# MainBoard_HMI.net
KiCad netlist of a schematic drawn in Altium Designer
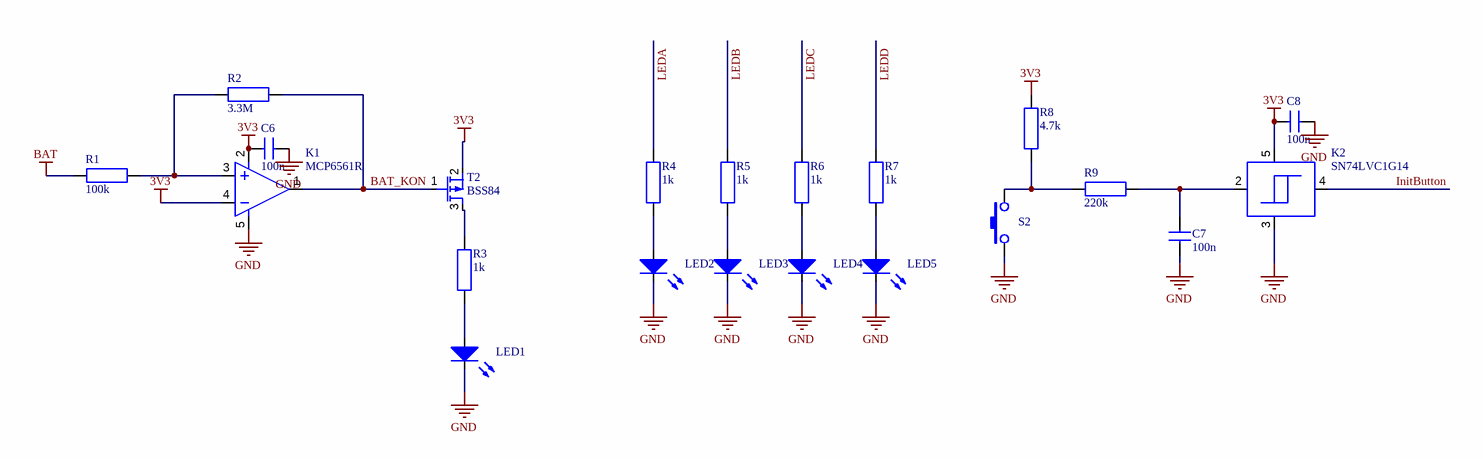
[diagram p0: MainBoard_HMI.SchDoc]

(export (version "E")
  (design (tool "Eeschema 10.0.6"))
  (components
    (comp (ref "C6")
      (value "100n")
      (footprint "0805_C")
      (description "Normaler Kondensator")
      (libsource (lib "MainBoard") (part "C?"))
    )
    (comp (ref "C7")
      (value "100n")
      (footprint "0805_C")
      (description "Normaler Kondensator")
      (libsource (lib "MainBoard") (part "C?"))
    )
    (comp (ref "C8")
      (value "100n")
      (footprint "0805_C")
      (description "Normaler Kondensator")
      (libsource (lib "MainBoard") (part "C?"))
    )
    (comp (ref "K1") (value "MCP6561R") (footprint "SOT23-5") (libsource (lib "MainBoard") (part "OPAMP")))
    (comp (ref "K2")
      (value "SN74LVC1G14")
      (footprint "SOT23-5")
      (libsource (lib "MainBoard") (part "schmitt"))
    )
    (comp (ref "LED1")
      (value "~")
      (footprint "LED_THT_3mm_RM_2.54mm")
      (libsource (lib "Sch_Lib") (part "LED"))
    )
    (comp (ref "LED2")
      (value "~")
      (footprint "LED_THT_3mm_RM_2.54mm")
      (libsource (lib "Sch_Lib") (part "LED"))
    )
    (comp (ref "LED3")
      (value "~")
      (footprint "LED_THT_3mm_RM_2.54mm")
      (libsource (lib "Sch_Lib") (part "LED"))
    )
    (comp (ref "LED4")
      (value "~")
      (footprint "LED_THT_3mm_RM_2.54mm")
      (libsource (lib "Sch_Lib") (part "LED"))
    )
    (comp (ref "LED5")
      (value "~")
      (footprint "LED_THT_3mm_RM_2.54mm")
      (libsource (lib "Sch_Lib") (part "LED"))
    )
    (comp (ref "R1")
      (value "100k")
      (footprint "0805_R")
      (description "Normaler Widerstand")
      (libsource (lib "MainBoard") (part "R?"))
    )
    (comp (ref "R2")
      (value "3.3M")
      (footprint "0805_R")
      (description "Normaler Widerstand")
      (libsource (lib "MainBoard") (part "R?"))
    )
    (comp (ref "R3")
      (value "1k")
      (footprint "0805_R")
      (description "Normaler Widerstand")
      (libsource (lib "MainBoard") (part "R?"))
    )
    (comp (ref "R4")
      (value "1k")
      (footprint "0805_R")
      (description "Normaler Widerstand")
      (libsource (lib "MainBoard") (part "R?"))
    )
    (comp (ref "R5")
      (value "1k")
      (footprint "0805_R")
      (description "Normaler Widerstand")
      (libsource (lib "MainBoard") (part "R?"))
    )
    (comp (ref "R6")
      (value "1k")
      (footprint "0805_R")
      (description "Normaler Widerstand")
      (libsource (lib "MainBoard") (part "R?"))
    )
    (comp (ref "R7")
      (value "1k")
      (footprint "0805_R")
      (description "Normaler Widerstand")
      (libsource (lib "MainBoard") (part "R?"))
    )
    (comp (ref "R8")
      (value "4.7k")
      (footprint "0805_R")
      (description "Normaler Widerstand")
      (libsource (lib "MainBoard") (part "R?"))
    )
    (comp (ref "R9")
      (value "220k")
      (footprint "0805_r")
      (description "Normaler Widerstand")
      (libsource (lib "MainBoard") (part "R?"))
    )
    (comp (ref "S2") (value "S2") (footprint "SIP2") (libsource (lib "DEVICE_HSLU") (part "SW-PB")))
    (comp (ref "T2")
      (value "BSS84")
      (footprint "SOT23-3")
      (description "MOSFET-P 1D,2G,3S")
      (libsource (lib "Sch_Lib") (part "MOSFET-P 1D,2G,3S"))
    )
  )
  (nets
    (net (code "1") (name "/BAT_KON") (class "Default")
      (node (ref "K1") (pin "1") (pinfunction "1_1") (pintype "passive"))
      (node (ref "R2") (pin "1") (pintype "passive"))
      (node (ref "T2") (pin "1") (pinfunction "G_1") (pintype "passive"))
    )
    (net (code "2") (name "/InitButton") (class "Default")
      (node (ref "K2") (pin "4") (pinfunction "4_4") (pintype "passive"))
    )
    (net (code "3") (name "/LEDA") (class "Default") (node (ref "R4") (pin "1") (pintype "passive")))
    (net (code "4") (name "/LEDB") (class "Default") (node (ref "R5") (pin "1") (pintype "passive")))
    (net (code "5") (name "/LEDC") (class "Default") (node (ref "R6") (pin "1") (pintype "passive")))
    (net (code "6") (name "/LEDD") (class "Default") (node (ref "R7") (pin "1") (pintype "passive")))
    (net (code "7") (name "3V3") (class "Default")
      (node (ref "C6") (pin "1") (pinfunction "1_1") (pintype "passive"))
      (node (ref "C8") (pin "1") (pinfunction "1_1") (pintype "passive"))
      (node (ref "K1") (pin "2") (pinfunction "2_2") (pintype "passive"))
      (node (ref "K1") (pin "4") (pinfunction "4_4") (pintype "passive"))
      (node (ref "K2") (pin "5") (pinfunction "5_5") (pintype "passive"))
      (node (ref "R8") (pin "1") (pintype "passive"))
      (node (ref "T2") (pin "2") (pinfunction "S_2") (pintype "passive"))
    )
    (net (code "8") (name "BAT") (class "Default") (node (ref "R1") (pin "2") (pintype "passive")))
    (net (code "9") (name "GND") (class "Default")
      (node (ref "C6") (pin "2") (pinfunction "2_2") (pintype "passive"))
      (node (ref "C7") (pin "1") (pinfunction "1_1") (pintype "passive"))
      (node (ref "C8") (pin "2") (pinfunction "2_2") (pintype "passive"))
      (node (ref "K1") (pin "5") (pinfunction "5_5") (pintype "passive"))
      (node (ref "K2") (pin "3") (pinfunction "3_3") (pintype "passive"))
      (node (ref "LED1") (pin "2") (pinfunction "K_2") (pintype "passive"))
      (node (ref "LED2") (pin "2") (pinfunction "K_2") (pintype "passive"))
      (node (ref "LED3") (pin "2") (pinfunction "K_2") (pintype "passive"))
      (node (ref "LED4") (pin "2") (pinfunction "K_2") (pintype "passive"))
      (node (ref "LED5") (pin "2") (pinfunction "K_2") (pintype "passive"))
      (node (ref "S2") (pin "1") (pintype "passive"))
    )
    (net (code "10") (name "Net-(C7-Pad2)") (class "Default")
      (node (ref "C7") (pin "2") (pinfunction "2_2") (pintype "passive"))
      (node (ref "K2") (pin "2") (pinfunction "2_2") (pintype "passive"))
      (node (ref "R9") (pin "2") (pintype "passive"))
    )
    (net (code "11") (name "Net-(K1-Pad3)") (class "Default")
      (node (ref "K1") (pin "3") (pinfunction "3_3") (pintype "passive"))
      (node (ref "R1") (pin "1") (pintype "passive"))
      (node (ref "R2") (pin "2") (pintype "passive"))
    )
    (net (code "12") (name "Net-(LED1-A)") (class "Default")
      (node (ref "LED1") (pin "1") (pinfunction "A_1") (pintype "passive"))
      (node (ref "R3") (pin "2") (pintype "passive"))
    )
    (net (code "13") (name "Net-(LED2-A)") (class "Default")
      (node (ref "LED2") (pin "1") (pinfunction "A_1") (pintype "passive"))
      (node (ref "R4") (pin "2") (pintype "passive"))
    )
    (net (code "14") (name "Net-(LED3-A)") (class "Default")
      (node (ref "LED3") (pin "1") (pinfunction "A_1") (pintype "passive"))
      (node (ref "R5") (pin "2") (pintype "passive"))
    )
    (net (code "15") (name "Net-(LED4-A)") (class "Default")
      (node (ref "LED4") (pin "1") (pinfunction "A_1") (pintype "passive"))
      (node (ref "R6") (pin "2") (pintype "passive"))
    )
    (net (code "16") (name "Net-(LED5-A)") (class "Default")
      (node (ref "LED5") (pin "1") (pinfunction "A_1") (pintype "passive"))
      (node (ref "R7") (pin "2") (pintype "passive"))
    )
    (net (code "17") (name "Net-(R8-Pad2)") (class "Default")
      (node (ref "R8") (pin "2") (pintype "passive"))
      (node (ref "R9") (pin "1") (pintype "passive"))
      (node (ref "S2") (pin "2") (pintype "passive"))
    )
    (net (code "18") (name "Net-(T2-D)") (class "Default")
      (node (ref "R3") (pin "1") (pintype "passive"))
      (node (ref "T2") (pin "3") (pinfunction "D_3") (pintype "passive"))
    )
  )
)
